# Adafruit_Metro_ESP32-S3.net
KiCad netlist of a schematic drawn in EAGLE
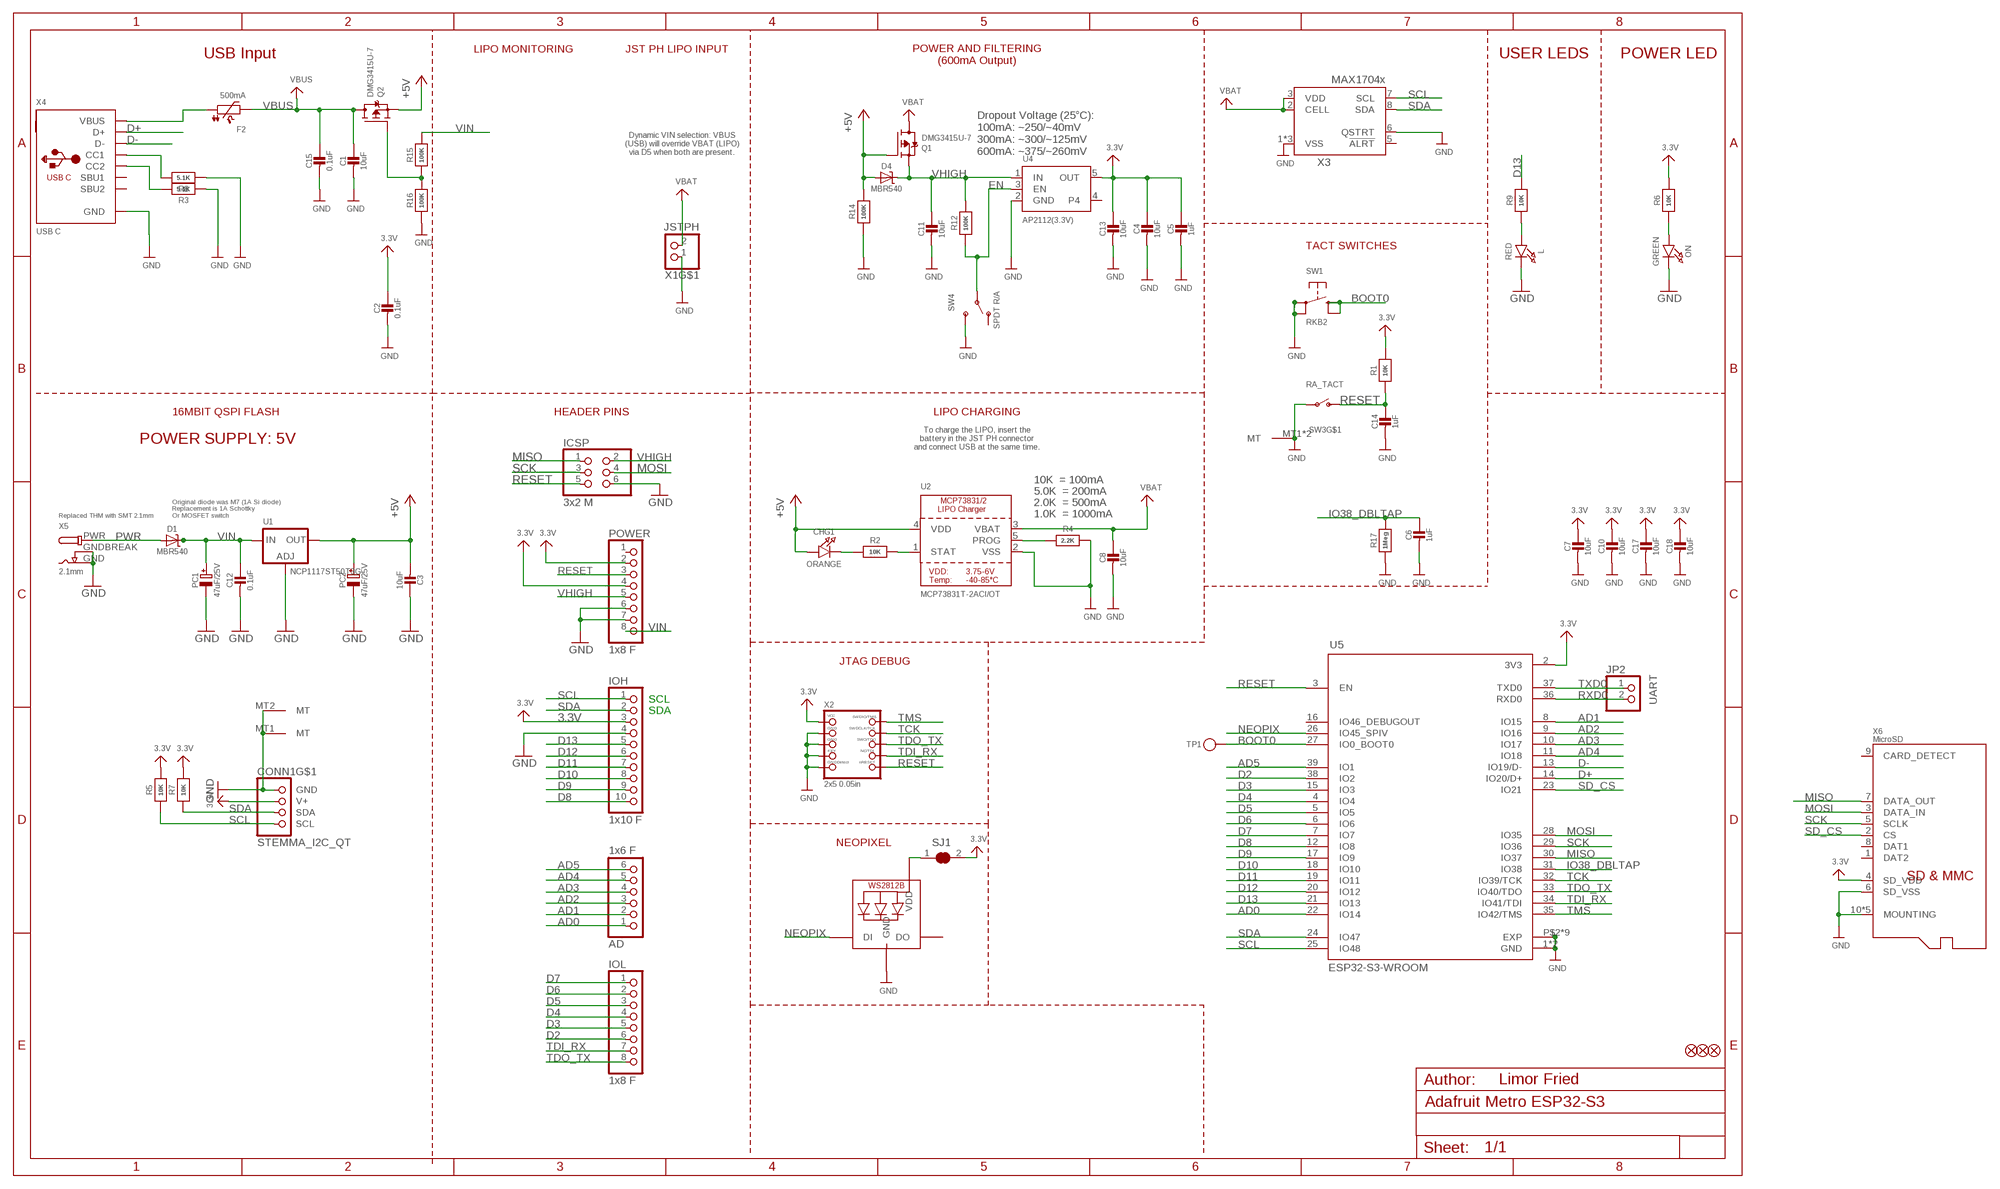
[diagram p0: schematic, sheet 1]

(export (version "E")
  (design (tool "Eeschema 10.0.6"))
  (components
    (comp (ref "AD")
      (value "1x6 F")
      (footprint "eagle-import:1X06_OVALWAVE")
      (libsource (lib "eagle-import") (part "HEADER-1X6OVALWAVE"))
    )
    (comp (ref "C1")
      (value "10uF")
      (footprint "eagle-import:0805-NO")
      (libsource (lib "eagle-import") (part "CAP_CERAMIC0805-NOOUTLINE"))
    )
    (comp (ref "C2")
      (value "0.1uF")
      (footprint "eagle-import:0603-NO")
      (libsource (lib "eagle-import") (part "CAP_CERAMIC0603_NO"))
    )
    (comp (ref "C3")
      (value "10uF")
      (footprint "eagle-import:0805-NO")
      (libsource (lib "eagle-import") (part "CAP_CERAMIC0805-NOOUTLINE"))
    )
    (comp (ref "C4")
      (value "10uF")
      (footprint "eagle-import:0805-NO")
      (libsource (lib "eagle-import") (part "CAP_CERAMIC0805-NOOUTLINE"))
    )
    (comp (ref "C5")
      (value "1uF")
      (footprint "eagle-import:0603-NO")
      (libsource (lib "eagle-import") (part "CAP_CERAMIC0603_NO"))
    )
    (comp (ref "C6")
      (value "1uF")
      (footprint "eagle-import:0603-NO")
      (libsource (lib "eagle-import") (part "CAP_CERAMIC0603_NO"))
    )
    (comp (ref "C7")
      (value "10uF")
      (footprint "eagle-import:0805-NO")
      (libsource (lib "eagle-import") (part "CAP_CERAMIC0805-NOOUTLINE"))
    )
    (comp (ref "C8")
      (value "10uF")
      (footprint "eagle-import:0805-NO")
      (libsource (lib "eagle-import") (part "CAP_CERAMIC0805-NOOUTLINE"))
    )
    (comp (ref "C10")
      (value "10uF")
      (footprint "eagle-import:0805-NO")
      (libsource (lib "eagle-import") (part "CAP_CERAMIC0805-NOOUTLINE"))
    )
    (comp (ref "C11")
      (value "10uF")
      (footprint "eagle-import:0805-NO")
      (libsource (lib "eagle-import") (part "CAP_CERAMIC0805-NOOUTLINE"))
    )
    (comp (ref "C12")
      (value "0.1uF")
      (footprint "eagle-import:0603-NO")
      (libsource (lib "eagle-import") (part "CAP_CERAMIC0603_NO"))
    )
    (comp (ref "C13")
      (value "10uF")
      (footprint "eagle-import:0805-NO")
      (libsource (lib "eagle-import") (part "CAP_CERAMIC0805-NOOUTLINE"))
    )
    (comp (ref "C14")
      (value "1uF")
      (footprint "eagle-import:0603-NO")
      (libsource (lib "eagle-import") (part "CAP_CERAMIC0603_NO"))
    )
    (comp (ref "C15")
      (value "0.1uF")
      (footprint "eagle-import:0603-NO")
      (libsource (lib "eagle-import") (part "CAP_CERAMIC0603_NO"))
    )
    (comp (ref "C17")
      (value "10uF")
      (footprint "eagle-import:0805-NO")
      (libsource (lib "eagle-import") (part "CAP_CERAMIC0805-NOOUTLINE"))
    )
    (comp (ref "C18")
      (value "10uF")
      (footprint "eagle-import:0805-NO")
      (libsource (lib "eagle-import") (part "CAP_CERAMIC0805-NOOUTLINE"))
    )
    (comp (ref "CHG1")
      (value "ORANGE")
      (footprint "eagle-import:CHIPLED_0603_NOOUTLINE")
      (libsource (lib "eagle-import") (part "LED0603_NOOUTLINE"))
    )
    (comp (ref "CONN1")
      (value "STEMMA_I2C_QT")
      (footprint "eagle-import:JST_SH4")
      (libsource (lib "eagle-import") (part "STEMMA_I2C_QT"))
    )
    (comp (ref "D1")
      (value "MBR540")
      (footprint "eagle-import:SOD-123")
      (libsource (lib "eagle-import") (part "DIODE-SCHOTTKYSOD-123"))
    )
    (comp (ref "D4")
      (value "MBR540")
      (footprint "eagle-import:SOD-123")
      (libsource (lib "eagle-import") (part "DIODE-SCHOTTKYSOD-123"))
    )
    (comp (ref "F2")
      (value "500mA")
      (footprint "eagle-import:0805-NO")
      (libsource (lib "eagle-import") (part "PTC_0805"))
    )
    (comp (ref "FD1")
      (value "FIDUCIAL_1MM")
      (footprint "eagle-import:FIDUCIAL_1MM")
      (libsource (lib "eagle-import") (part "FIDUCIAL_1MM"))
    )
    (comp (ref "FD2")
      (value "FIDUCIAL_1MM")
      (footprint "eagle-import:FIDUCIAL_1MM")
      (libsource (lib "eagle-import") (part "FIDUCIAL_1MM"))
    )
    (comp (ref "FD3")
      (value "FIDUCIAL_1MM")
      (footprint "eagle-import:FIDUCIAL_1MM")
      (libsource (lib "eagle-import") (part "FIDUCIAL_1MM"))
    )
    (comp (ref "ICSP")
      (value "3x2 M")
      (footprint "eagle-import:2X03_ROUND_70MIL")
      (libsource (lib "eagle-import") (part "HEADER-2X3"))
    )
    (comp (ref "IOH")
      (value "1x10 F")
      (footprint "eagle-import:1X10_OVALWAVE")
      (libsource (lib "eagle-import") (part "HEADER-1X10OVALWAVE"))
    )
    (comp (ref "IOL")
      (value "1x8 F")
      (footprint "eagle-import:1X08_OVALWAVE")
      (libsource (lib "eagle-import") (part "HEADER-1X8OVALWAVE"))
    )
    (comp (ref "JP2")
      (value "UART")
      (footprint "eagle-import:1X02_ROUND")
      (libsource (lib "eagle-import") (part "HEADER-1X2ROUND"))
    )
    (comp (ref "L")
      (value "RED")
      (footprint "eagle-import:CHIPLED_0603_NOOUTLINE")
      (libsource (lib "eagle-import") (part "LED0603_NOOUTLINE"))
    )
    (comp (ref "LED1")
      (value "WS2812B_3535FULL")
      (footprint "eagle-import:LED3535_FULLPADS")
      (libsource (lib "eagle-import") (part "WS2812B_3535FULL"))
    )
    (comp (ref "ON")
      (value "GREEN")
      (footprint "eagle-import:CHIPLED_0603_NOOUTLINE")
      (libsource (lib "eagle-import") (part "LED0603_NOOUTLINE"))
    )
    (comp (ref "PC1")
      (value "47uF/25V")
      (footprint "eagle-import:PANASONIC_D")
      (libsource (lib "eagle-import") (part "CAP_ELECTROLYTICPANASONIC_D"))
    )
    (comp (ref "PC2")
      (value "47uF/25V")
      (footprint "eagle-import:PANASONIC_D")
      (libsource (lib "eagle-import") (part "CAP_ELECTROLYTICPANASONIC_D"))
    )
    (comp (ref "POWER")
      (value "1x8 F")
      (footprint "eagle-import:1X08_OVALWAVE")
      (libsource (lib "eagle-import") (part "HEADER-1X8OVALWAVE"))
    )
    (comp (ref "Q1")
      (value "DMG3415U-7")
      (footprint "eagle-import:SOT23-R")
      (libsource (lib "eagle-import") (part "MOSFET-P"))
    )
    (comp (ref "Q2")
      (value "DMG3415U-7")
      (footprint "eagle-import:SOT23-R")
      (libsource (lib "eagle-import") (part "MOSFET-P"))
    )
    (comp (ref "R1")
      (value "10K")
      (footprint "eagle-import:0603-NO")
      (libsource (lib "eagle-import") (part "RESISTOR_0603_NOOUT"))
    )
    (comp (ref "R2")
      (value "10K")
      (footprint "eagle-import:0603-NO")
      (libsource (lib "eagle-import") (part "RESISTOR_0603_NOOUT"))
    )
    (comp (ref "R3")
      (value "5.1K")
      (footprint "eagle-import:0603-NO")
      (libsource (lib "eagle-import") (part "RESISTOR_0603_NOOUT"))
    )
    (comp (ref "R4")
      (value "2.2K")
      (footprint "eagle-import:0603-NO")
      (libsource (lib "eagle-import") (part "RESISTOR_0603_NOOUT"))
    )
    (comp (ref "R5")
      (value "10K")
      (footprint "eagle-import:0603-NO")
      (libsource (lib "eagle-import") (part "RESISTOR_0603_NOOUT"))
    )
    (comp (ref "R6")
      (value "10K")
      (footprint "eagle-import:0603-NO")
      (libsource (lib "eagle-import") (part "RESISTOR_0603_NOOUT"))
    )
    (comp (ref "R7")
      (value "10K")
      (footprint "eagle-import:0603-NO")
      (libsource (lib "eagle-import") (part "RESISTOR_0603_NOOUT"))
    )
    (comp (ref "R8")
      (value "5.1K")
      (footprint "eagle-import:0603-NO")
      (libsource (lib "eagle-import") (part "RESISTOR_0603_NOOUT"))
    )
    (comp (ref "R9")
      (value "10K")
      (footprint "eagle-import:0603-NO")
      (libsource (lib "eagle-import") (part "RESISTOR_0603_NOOUT"))
    )
    (comp (ref "R12")
      (value "100K")
      (footprint "eagle-import:0603-NO")
      (libsource (lib "eagle-import") (part "RESISTOR_0603_NOOUT"))
    )
    (comp (ref "R14")
      (value "100K")
      (footprint "eagle-import:0603-NO")
      (libsource (lib "eagle-import") (part "RESISTOR_0603_NOOUT"))
    )
    (comp (ref "R15")
      (value "100K")
      (footprint "eagle-import:0603-NO")
      (libsource (lib "eagle-import") (part "RESISTOR_0603_NOOUT"))
    )
    (comp (ref "R16")
      (value "100K")
      (footprint "eagle-import:0603-NO")
      (libsource (lib "eagle-import") (part "RESISTOR_0603_NOOUT"))
    )
    (comp (ref "R17")
      (value "1Meg")
      (footprint "eagle-import:0603-NO")
      (libsource (lib "eagle-import") (part "RESISTOR_0603_NOOUT"))
    )
    (comp (ref "SJ1")
      (value "SOLDERJUMPER_CLOSED")
      (footprint "eagle-import:SOLDERJUMPER_CLOSEDWIRE")
      (libsource (lib "eagle-import") (part "SOLDERJUMPER_CLOSED"))
    )
    (comp (ref "SW1")
      (value "RKB2")
      (footprint "eagle-import:BTN_RKB2_4.6X2.8")
      (libsource (lib "eagle-import") (part "SWITCH_TACT_SMT_RKB2"))
    )
    (comp (ref "SW3")
      (value "RA_TACT")
      (footprint "eagle-import:SPST_TACTILE_RA")
      (libsource (lib "eagle-import") (part "SWITCH_SPST_MNT_TACT_RA"))
    )
    (comp (ref "SW4")
      (value "SPDT R/A")
      (footprint "eagle-import:SPDT_SMT_SSSS811101")
      (libsource (lib "eagle-import") (part "SWITCH_SPDT"))
    )
    (comp (ref "TP1")
      (value "TESTPOINTROUND1.5MMNO")
      (footprint "eagle-import:TESTPOINT_ROUND_1.5MM_NO")
      (libsource (lib "eagle-import") (part "TESTPOINTROUND1.5MMNO"))
    )
    (comp (ref "U1")
      (value "NCP1117ST50T3G")
      (footprint "eagle-import:SOT223-R")
      (libsource (lib "eagle-import") (part "LM1117SOT223-REFLOW"))
    )
    (comp (ref "U2")
      (value "MCP73831T-2ACI/OT")
      (footprint "eagle-import:SOT23-5")
      (libsource (lib "eagle-import") (part "MCP73831/2"))
    )
    (comp (ref "U4")
      (value "AP2112(3.3V)")
      (footprint "eagle-import:SOT23-5")
      (fields (field (name "JLC_ROTATION") "0"))
      (libsource (lib "eagle-import") (part "VREG_SOT23-5"))
    )
    (comp (ref "U5")
      (value "ESP32-S3-WROOM")
      (footprint "eagle-import:S3-WROOM32")
      (libsource (lib "eagle-import") (part "ESP32-S3-WROOM"))
    )
    (comp (ref "X1")
      (value "JSTPH")
      (footprint "eagle-import:JSTPH2_BATT")
      (libsource (lib "eagle-import") (part "CON_JST_PH_2PIN_MT_BATT"))
    )
    (comp (ref "X2")
      (value "2x5 0.05in")
      (footprint "eagle-import:2X05_1.27MM_BOX_POSTS")
      (libsource (lib "eagle-import") (part "JTAG-CORTEXBOXPOSTS"))
    )
    (comp (ref "X3")
      (value "MAX17048/T")
      (footprint "eagle-import:TDFN8_2X2MM")
      (libsource (lib "eagle-import") (part "MAX17048/T"))
    )
    (comp (ref "X4")
      (value "USB C")
      (footprint "eagle-import:USB_C_CUSB31-CFM2AX-01-X")
      (libsource (lib "eagle-import") (part "USB_C"))
    )
    (comp (ref "X5")
      (value "2.1mm")
      (footprint "eagle-import:DCJACK_2MM_PTH")
      (libsource (lib "eagle-import") (part "DCBARRELPTH"))
    )
    (comp (ref "X6")
      (value "MicroSD")
      (footprint "eagle-import:MOLEX_104031-0811")
      (libsource (lib "eagle-import") (part "MICROSD104031-0811"))
    )
  )
  (nets
    (net (code "1") (name "+5V") (class "Default")
      (node (ref "C3") (pin "2") (pinfunction "2_2") (pintype "passive"))
      (node (ref "CHG1") (pin "A") (pinfunction "A_A") (pintype "passive"))
      (node (ref "D4") (pin "A") (pinfunction "A_A") (pintype "passive"))
      (node (ref "PC2") (pin "+") (pinfunction "+_+") (pintype "passive"))
      (node (ref "Q1") (pin "1") (pinfunction "G_1") (pintype "passive"))
      (node (ref "Q2") (pin "2") (pinfunction "S_2") (pintype "passive"))
      (node (ref "R14") (pin "2") (pinfunction "2_2") (pintype "passive"))
      (node (ref "U1") (pin "2") (pinfunction "OUT_2") (pintype "passive"))
      (node (ref "U1") (pin "4") (pinfunction "OUT_4") (pintype "passive"))
      (node (ref "U2") (pin "4") (pinfunction "VDD_4") (pintype "power_in"))
    )
    (net (code "2") (name "/AD0") (class "Default")
      (node (ref "AD") (pin "1") (pinfunction "1_1") (pintype "passive"))
      (node (ref "U5") (pin "22") (pinfunction "IO14_22") (pintype "bidirectional"))
    )
    (net (code "3") (name "/AD1") (class "Default")
      (node (ref "AD") (pin "2") (pinfunction "2_2") (pintype "passive"))
      (node (ref "U5") (pin "8") (pinfunction "IO15_8") (pintype "bidirectional"))
    )
    (net (code "4") (name "/AD2") (class "Default")
      (node (ref "AD") (pin "3") (pinfunction "3_3") (pintype "passive"))
      (node (ref "U5") (pin "9") (pinfunction "IO16_9") (pintype "bidirectional"))
    )
    (net (code "5") (name "/AD3") (class "Default")
      (node (ref "AD") (pin "4") (pinfunction "4_4") (pintype "passive"))
      (node (ref "U5") (pin "10") (pinfunction "IO17_10") (pintype "bidirectional"))
    )
    (net (code "6") (name "/AD4") (class "Default")
      (node (ref "AD") (pin "5") (pinfunction "5_5") (pintype "passive"))
      (node (ref "U5") (pin "11") (pinfunction "IO18_11") (pintype "bidirectional"))
    )
    (net (code "7") (name "/AD5") (class "Default")
      (node (ref "AD") (pin "6") (pinfunction "6_6") (pintype "passive"))
      (node (ref "U5") (pin "39") (pinfunction "IO1_39") (pintype "bidirectional"))
    )
    (net (code "8") (name "/BOOT0") (class "Default")
      (node (ref "SW1") (pin "B") (pinfunction "S_B") (pintype "passive"))
      (node (ref "SW1") (pin "B'") (pinfunction "S1_B'") (pintype "passive"))
      (node (ref "TP1") (pin "P$1") (pinfunction "P$1_P$1") (pintype "bidirectional"))
      (node (ref "U5") (pin "27") (pinfunction "IO0_BOOT0_27") (pintype "bidirectional"))
    )
    (net (code "9") (name "/D+") (class "Default")
      (node (ref "U5") (pin "14") (pinfunction "IO20/D+_14") (pintype "bidirectional"))
      (node (ref "X4") (pin "A6") (pinfunction "D+_A6") (pintype "bidirectional"))
      (node (ref "X4") (pin "B6") (pinfunction "D+_B6") (pintype "bidirectional"))
    )
    (net (code "10") (name "/D-") (class "Default")
      (node (ref "U5") (pin "13") (pinfunction "IO19/D-_13") (pintype "bidirectional"))
      (node (ref "X4") (pin "A7") (pinfunction "D-_A7") (pintype "bidirectional"))
      (node (ref "X4") (pin "B7") (pinfunction "D-_B7") (pintype "bidirectional"))
    )
    (net (code "11") (name "/D2") (class "Default")
      (node (ref "IOL") (pin "6") (pinfunction "6_6") (pintype "passive"))
      (node (ref "U5") (pin "38") (pinfunction "IO2_38") (pintype "bidirectional"))
    )
    (net (code "12") (name "/D3") (class "Default")
      (node (ref "IOL") (pin "5") (pinfunction "5_5") (pintype "passive"))
      (node (ref "U5") (pin "15") (pinfunction "IO3_15") (pintype "bidirectional"))
    )
    (net (code "13") (name "/D4") (class "Default")
      (node (ref "IOL") (pin "4") (pinfunction "4_4") (pintype "passive"))
      (node (ref "U5") (pin "4") (pinfunction "IO4_4") (pintype "bidirectional"))
    )
    (net (code "14") (name "/D5") (class "Default")
      (node (ref "IOL") (pin "3") (pinfunction "3_3") (pintype "passive"))
      (node (ref "U5") (pin "5") (pinfunction "IO5_5") (pintype "bidirectional"))
    )
    (net (code "15") (name "/D6") (class "Default")
      (node (ref "IOL") (pin "2") (pinfunction "2_2") (pintype "passive"))
      (node (ref "U5") (pin "6") (pinfunction "IO6_6") (pintype "bidirectional"))
    )
    (net (code "16") (name "/D7") (class "Default")
      (node (ref "IOL") (pin "1") (pinfunction "1_1") (pintype "passive"))
      (node (ref "U5") (pin "7") (pinfunction "IO7_7") (pintype "bidirectional"))
    )
    (net (code "17") (name "/D8") (class "Default")
      (node (ref "IOH") (pin "10") (pinfunction "10_10") (pintype "passive"))
      (node (ref "U5") (pin "12") (pinfunction "IO8_12") (pintype "bidirectional"))
    )
    (net (code "18") (name "/D9") (class "Default")
      (node (ref "IOH") (pin "9") (pinfunction "9_9") (pintype "passive"))
      (node (ref "U5") (pin "17") (pinfunction "IO9_17") (pintype "bidirectional"))
    )
    (net (code "19") (name "/D10") (class "Default")
      (node (ref "IOH") (pin "8") (pinfunction "8_8") (pintype "passive"))
      (node (ref "U5") (pin "18") (pinfunction "IO10_18") (pintype "bidirectional"))
    )
    (net (code "20") (name "/D11") (class "Default")
      (node (ref "IOH") (pin "7") (pinfunction "7_7") (pintype "passive"))
      (node (ref "U5") (pin "19") (pinfunction "IO11_19") (pintype "bidirectional"))
    )
    (net (code "21") (name "/D12") (class "Default")
      (node (ref "IOH") (pin "6") (pinfunction "6_6") (pintype "passive"))
      (node (ref "U5") (pin "20") (pinfunction "IO12_20") (pintype "bidirectional"))
    )
    (net (code "22") (name "/D13") (class "Default")
      (node (ref "IOH") (pin "5") (pinfunction "5_5") (pintype "passive"))
      (node (ref "R9") (pin "2") (pinfunction "2_2") (pintype "passive"))
      (node (ref "U5") (pin "21") (pinfunction "IO13_21") (pintype "bidirectional"))
    )
    (net (code "23") (name "/EN") (class "Default")
      (node (ref "R12") (pin "1") (pinfunction "1_1") (pintype "passive"))
      (node (ref "SW4") (pin "B") (pinfunction "P_B") (pintype "passive"))
      (node (ref "U4") (pin "3") (pinfunction "EN_3") (pintype "input"))
    )
    (net (code "24") (name "/IO38_DBLTAP") (class "Default")
      (node (ref "C6") (pin "1") (pinfunction "1_1") (pintype "passive"))
      (node (ref "R17") (pin "2") (pinfunction "2_2") (pintype "passive"))
      (node (ref "U5") (pin "31") (pinfunction "IO38_31") (pintype "bidirectional"))
    )
    (net (code "25") (name "/MISO") (class "Default")
      (node (ref "ICSP") (pin "1") (pinfunction "1_1") (pintype "passive"))
      (node (ref "U5") (pin "30") (pinfunction "IO37_30") (pintype "bidirectional"))
      (node (ref "X6") (pin "7") (pinfunction "DATA_OUT_7") (pintype "output"))
    )
    (net (code "26") (name "/MOSI") (class "Default")
      (node (ref "ICSP") (pin "4") (pinfunction "4_4") (pintype "passive"))
      (node (ref "U5") (pin "28") (pinfunction "IO35_28") (pintype "input"))
      (node (ref "X6") (pin "3") (pinfunction "DATA_IN_3") (pintype "input"))
    )
    (net (code "27") (name "/NEOPIX") (class "Default")
      (node (ref "LED1") (pin "1") (pinfunction "DI_1") (pintype "input"))
      (node (ref "U5") (pin "26") (pinfunction "IO45_SPIV_26") (pintype "bidirectional"))
    )
    (net (code "28") (name "/PWR") (class "Default")
      (node (ref "D1") (pin "A") (pinfunction "A_A") (pintype "passive"))
      (node (ref "X5") (pin "PWR") (pinfunction "PWR_PWR") (pintype "power_in"))
    )
    (net (code "29") (name "/RESET") (class "Default")
      (node (ref "C14") (pin "1") (pinfunction "1_1") (pintype "passive"))
      (node (ref "ICSP") (pin "5") (pinfunction "5_5") (pintype "passive"))
      (node (ref "POWER") (pin "3") (pinfunction "3_3") (pintype "passive"))
      (node (ref "R1") (pin "1") (pinfunction "1_1") (pintype "passive"))
      (node (ref "SW3") (pin "2") (pinfunction "S_2") (pintype "passive"))
      (node (ref "U5") (pin "3") (pinfunction "EN_3") (pintype "input"))
      (node (ref "X2") (pin "10") (pinfunction "NRESET_10") (pintype "bidirectional"))
    )
    (net (code "30") (name "/RXD0") (class "Default")
      (node (ref "JP2") (pin "2") (pinfunction "2_2") (pintype "passive"))
      (node (ref "U5") (pin "36") (pinfunction "RXD0_36") (pintype "bidirectional"))
    )
    (net (code "31") (name "/SCK") (class "Default")
      (node (ref "ICSP") (pin "3") (pinfunction "3_3") (pintype "passive"))
      (node (ref "U5") (pin "29") (pinfunction "IO36_29") (pintype "bidirectional"))
      (node (ref "X6") (pin "5") (pinfunction "SCLK_5") (pintype "input"))
    )
    (net (code "32") (name "/SCL") (class "Default")
      (node (ref "CONN1") (pin "4") (pinfunction "SCL_4") (pintype "passive"))
      (node (ref "IOH") (pin "1") (pinfunction "1_1") (pintype "passive"))
      (node (ref "R5") (pin "1") (pinfunction "1_1") (pintype "passive"))
      (node (ref "U5") (pin "25") (pinfunction "IO48_25") (pintype "input"))
      (node (ref "X3") (pin "7") (pinfunction "SCL_7") (pintype "bidirectional"))
    )
    (net (code "33") (name "/SDA") (class "Default")
      (node (ref "CONN1") (pin "3") (pinfunction "SDA_3") (pintype "passive"))
      (node (ref "IOH") (pin "2") (pinfunction "2_2") (pintype "passive"))
      (node (ref "R7") (pin "1") (pinfunction "1_1") (pintype "passive"))
      (node (ref "U5") (pin "24") (pinfunction "IO47_24") (pintype "bidirectional"))
      (node (ref "X3") (pin "8") (pinfunction "SDA_8") (pintype "bidirectional"))
    )
    (net (code "34") (name "/SD_CS") (class "Default")
      (node (ref "U5") (pin "23") (pinfunction "IO21_23") (pintype "bidirectional"))
      (node (ref "X6") (pin "2") (pinfunction "CS_2") (pintype "input"))
    )
    (net (code "35") (name "/TCK") (class "Default")
      (node (ref "U5") (pin "32") (pinfunction "IO39/TCK_32") (pintype "bidirectional"))
      (node (ref "X2") (pin "4") (pinfunction "SWDCLK_4") (pintype "bidirectional"))
    )
    (net (code "36") (name "/TDI_RX") (class "Default")
      (node (ref "IOL") (pin "7") (pinfunction "7_7") (pintype "passive"))
      (node (ref "U5") (pin "34") (pinfunction "IO41/TDI_34") (pintype "bidirectional"))
      (node (ref "X2") (pin "8") (pinfunction "TDI_8") (pintype "bidirectional"))
    )
    (net (code "37") (name "/TDO_TX") (class "Default")
      (node (ref "IOL") (pin "8") (pinfunction "8_8") (pintype "passive"))
      (node (ref "U5") (pin "33") (pinfunction "IO40/TDO_33") (pintype "bidirectional"))
      (node (ref "X2") (pin "6") (pinfunction "SWO_6") (pintype "bidirectional"))
    )
    (net (code "38") (name "/TMS") (class "Default")
      (node (ref "U5") (pin "35") (pinfunction "IO42/TMS_35") (pintype "bidirectional"))
      (node (ref "X2") (pin "2") (pinfunction "SWDIO_2") (pintype "bidirectional"))
    )
    (net (code "39") (name "/TXD0") (class "Default")
      (node (ref "JP2") (pin "1") (pinfunction "1_1") (pintype "passive"))
      (node (ref "U5") (pin "37") (pinfunction "TXD0_37") (pintype "bidirectional"))
    )
    (net (code "40") (name "/VHIGH") (class "Default")
      (node (ref "C11") (pin "1") (pinfunction "1_1") (pintype "passive"))
      (node (ref "D4") (pin "C") (pinfunction "C_C") (pintype "passive"))
      (node (ref "ICSP") (pin "2") (pinfunction "2_2") (pintype "passive"))
      (node (ref "POWER") (pin "5") (pinfunction "5_5") (pintype "passive"))
      (node (ref "Q1") (pin "2") (pinfunction "S_2") (pintype "passive"))
      (node (ref "R12") (pin "2") (pinfunction "2_2") (pintype "passive"))
      (node (ref "U4") (pin "1") (pinfunction "IN_1") (pintype "power_in"))
    )
    (net (code "41") (name "/VIN") (class "Default")
      (node (ref "C12") (pin "1") (pinfunction "1_1") (pintype "passive"))
      (node (ref "D1") (pin "C") (pinfunction "C_C") (pintype "passive"))
      (node (ref "PC1") (pin "+") (pinfunction "+_+") (pintype "passive"))
      (node (ref "POWER") (pin "8") (pinfunction "8_8") (pintype "passive"))
      (node (ref "R15") (pin "2") (pinfunction "2_2") (pintype "passive"))
      (node (ref "U1") (pin "3") (pinfunction "IN_3") (pintype "input"))
    )
    (net (code "42") (name "3.3V") (class "Default")
      (node (ref "C10") (pin "1") (pinfunction "1_1") (pintype "passive"))
      (node (ref "C13") (pin "1") (pinfunction "1_1") (pintype "passive"))
      (node (ref "C17") (pin "1") (pinfunction "1_1") (pintype "passive"))
      (node (ref "C18") (pin "1") (pinfunction "1_1") (pintype "passive"))
      (node (ref "C2") (pin "1") (pinfunction "1_1") (pintype "passive"))
      (node (ref "C4") (pin "1") (pinfunction "1_1") (pintype "passive"))
      (node (ref "C5") (pin "1") (pinfunction "1_1") (pintype "passive"))
      (node (ref "C7") (pin "1") (pinfunction "1_1") (pintype "passive"))
      (node (ref "CONN1") (pin "2") (pinfunction "V+_2") (pintype "passive"))
      (node (ref "IOH") (pin "3") (pinfunction "3_3") (pintype "passive"))
      (node (ref "POWER") (pin "2") (pinfunction "2_2") (pintype "passive"))
      (node (ref "POWER") (pin "4") (pinfunction "4_4") (pintype "passive"))
      (node (ref "R1") (pin "2") (pinfunction "2_2") (pintype "passive"))
      (node (ref "R5") (pin "2") (pinfunction "2_2") (pintype "passive"))
      (node (ref "R6") (pin "2") (pinfunction "2_2") (pintype "passive"))
      (node (ref "R7") (pin "2") (pinfunction "2_2") (pintype "passive"))
      (node (ref "SJ1") (pin "2") (pinfunction "2_2") (pintype "passive"))
      (node (ref "U4") (pin "5") (pinfunction "OUT_5") (pintype "power_in"))
      (node (ref "U5") (pin "2") (pinfunction "3V3_2") (pintype "power_in"))
      (node (ref "X2") (pin "1") (pinfunction "VCC_1") (pintype "power_in"))
      (node (ref "X6") (pin "4") (pinfunction "SD_VDD_4") (pintype "power_in"))
    )
    (net (code "43") (name "GND") (class "Default")
      (node (ref "C1") (pin "2") (pinfunction "2_2") (pintype "passive"))
      (node (ref "C10") (pin "2") (pinfunction "2_2") (pintype "passive"))
      (node (ref "C11") (pin "2") (pinfunction "2_2") (pintype "passive"))
      (node (ref "C12") (pin "2") (pinfunction "2_2") (pintype "passive"))
      (node (ref "C13") (pin "2") (pinfunction "2_2") (pintype "passive"))
      (node (ref "C14") (pin "2") (pinfunction "2_2") (pintype "passive"))
      (node (ref "C15") (pin "2") (pinfunction "2_2") (pintype "passive"))
      (node (ref "C17") (pin "2") (pinfunction "2_2") (pintype "passive"))
      (node (ref "C18") (pin "2") (pinfunction "2_2") (pintype "passive"))
      (node (ref "C2") (pin "2") (pinfunction "2_2") (pintype "passive"))
      (node (ref "C3") (pin "1") (pinfunction "1_1") (pintype "passive"))
      (node (ref "C4") (pin "2") (pinfunction "2_2") (pintype "passive"))
      (node (ref "C5") (pin "2") (pinfunction "2_2") (pintype "passive"))
      (node (ref "C6") (pin "2") (pinfunction "2_2") (pintype "passive"))
      (node (ref "C7") (pin "2") (pinfunction "2_2") (pintype "passive"))
      (node (ref "C8") (pin "2") (pinfunction "2_2") (pintype "passive"))
      (node (ref "CONN1") (pin "1") (pinfunction "GND_1") (pintype "passive"))
      (node (ref "CONN1") (pin "MT1") (pinfunction "MT_MT1") (pintype "bidirectional"))
      (node (ref "CONN1") (pin "MT2") (pinfunction "MT_MT2") (pintype "bidirectional"))
      (node (ref "ICSP") (pin "6") (pinfunction "6_6") (pintype "passive"))
      (node (ref "IOH") (pin "4") (pinfunction "4_4") (pintype "passive"))
      (node (ref "L") (pin "C") (pinfunction "C_C") (pintype "passive"))
      (node (ref "LED1") (pin "4") (pinfunction "GND_4") (pintype "power_in"))
      (node (ref "ON") (pin "C") (pinfunction "C_C") (pintype "passive"))
      (node (ref "PC1") (pin "-") (pinfunction "-_-") (pintype "passive"))
      (node (ref "PC2") (pin "-") (pinfunction "-_-") (pintype "passive"))
      (node (ref "POWER") (pin "6") (pinfunction "6_6") (pintype "passive"))
      (node (ref "POWER") (pin "7") (pinfunction "7_7") (pintype "passive"))
      (node (ref "R14") (pin "1") (pinfunction "1_1") (pintype "passive"))
      (node (ref "R16") (pin "1") (pinfunction "1_1") (pintype "passive"))
      (node (ref "R17") (pin "1") (pinfunction "1_1") (pintype "passive"))
      (node (ref "R3") (pin "1") (pinfunction "1_1") (pintype "passive"))
      (node (ref "R4") (pin "2") (pinfunction "2_2") (pintype "passive"))
      (node (ref "R8") (pin "1") (pinfunction "1_1") (pintype "passive"))
      (node (ref "SW1") (pin "A") (pinfunction "P_A") (pintype "passive"))
      (node (ref "SW1") (pin "A'") (pinfunction "P1_A'") (pintype "passive"))
      (node (ref "SW3") (pin "1") (pinfunction "P_1") (pintype "passive"))
      (node (ref "SW3") (pin "MT1") (pinfunction "MT_MT1") (pintype "bidirectional"))
      (node (ref "SW3") (pin "MT2") (pinfunction "MT_MT2") (pintype "bidirectional"))
      (node (ref "SW4") (pin "C") (pinfunction "S_C") (pintype "passive"))
      (node (ref "U1") (pin "1") (pinfunction "ADJ_1") (pintype "input"))
      (node (ref "U2") (pin "2") (pinfunction "VSS_2") (pintype "power_in"))
      (node (ref "U4") (pin "2") (pinfunction "GND_2") (pintype "power_in"))
      (node (ref "U5") (pin "1") (pinfunction "GND_1") (pintype "power_in"))
      (node (ref "U5") (pin "40") (pinfunction "GND_40") (pintype "power_in"))
      (node (ref "U5") (pin "P$10") (pinfunction "EXP_P$10") (pintype "power_in"))
      (node (ref "U5") (pin "P$2") (pinfunction "EXP_P$2") (pintype "power_in"))
      (node (ref "U5") (pin "P$3") (pinfunction "EXP_P$3") (pintype "power_in"))
      (node (ref "U5") (pin "P$4") (pinfunction "EXP_P$4") (pintype "power_in"))
      (node (ref "U5") (pin "P$5") (pinfunction "EXP_P$5") (pintype "power_in"))
      (node (ref "U5") (pin "P$6") (pinfunction "EXP_P$6") (pintype "power_in"))
      (node (ref "U5") (pin "P$7") (pinfunction "EXP_P$7") (pintype "power_in"))
      (node (ref "U5") (pin "P$8") (pinfunction "EXP_P$8") (pintype "power_in"))
      (node (ref "U5") (pin "P$9") (pinfunction "EXP_P$9") (pintype "power_in"))
      (node (ref "X1") (pin "1") (pinfunction "1_1") (pintype "passive"))
      (node (ref "X2") (pin "3") (pinfunction "GND_3") (pintype "power_in"))
      (node (ref "X2") (pin "5") (pinfunction "GND_5") (pintype "power_in"))
      (node (ref "X2") (pin "7") (pinfunction "KEY_7") (pintype "bidirectional"))
      (node (ref "X2") (pin "9") (pinfunction "GNDDETECT_9") (pintype "bidirectional"))
      (node (ref "X3") (pin "1") (pinfunction "VSS_1") (pintype "power_in"))
      (node (ref "X3") (pin "4") (pinfunction "VSS_4") (pintype "power_in"))
      (node (ref "X3") (pin "6") (pinfunction "QSTRT_6") (pintype "input"))
      (node (ref "X3") (pin "THERMAL") (pinfunction "VSS_THERMAL") (pintype "power_in"))
      (node (ref "X4") (pin "A1B12") (pinfunction "GND_A1B12") (pintype "power_in"))
      (node (ref "X4") (pin "B1A12") (pinfunction "GND_B1A12") (pintype "power_in"))
      (node (ref "X5") (pin "GND") (pinfunction "GND_GND") (pintype "power_in"))
      (node (ref "X5") (pin "GNDBREAK") (pinfunction "GNDBREAK_GNDBREAK") (pintype "power_in"))
      (node (ref "X6") (pin "10") (pinfunction "MOUNTING_10") (pintype "passive"))
      (node (ref "X6") (pin "6") (pinfunction "SD_VSS_6") (pintype "power_in"))
      (node (ref "X6") (pin "G1") (pinfunction "MOUNTING_G1") (pintype "passive"))
      (node (ref "X6") (pin "G2") (pinfunction "MOUNTING_G2") (pintype "passive"))
      (node (ref "X6") (pin "G3") (pinfunction "MOUNTING_G3") (pintype "passive"))
      (node (ref "X6") (pin "G4") (pinfunction "MOUNTING_G4") (pintype "passive"))
    )
    (net (code "44") (name "Net-(CHG1-PadC)") (class "Default")
      (node (ref "CHG1") (pin "C") (pinfunction "C_C") (pintype "passive"))
      (node (ref "R2") (pin "1") (pinfunction "1_1") (pintype "passive"))
    )
    (net (code "45") (name "Net-(F2-Pad1)") (class "Default")
      (node (ref "F2") (pin "1") (pinfunction "1_1") (pintype "passive"))
      (node (ref "X4") (pin "A4B9") (pinfunction "VBUS_A4B9") (pintype "power_in"))
      (node (ref "X4") (pin "B4A9") (pinfunction "VBUS_B4A9") (pintype "power_in"))
    )
    (net (code "46") (name "Net-(L-PadA)") (class "Default")
      (node (ref "L") (pin "A") (pinfunction "A_A") (pintype "passive"))
      (node (ref "R9") (pin "1") (pinfunction "1_1") (pintype "passive"))
    )
    (net (code "47") (name "Net-(LED1-VDD)") (class "Default")
      (node (ref "LED1") (pin "2") (pinfunction "VDD_2") (pintype "power_in"))
      (node (ref "SJ1") (pin "1") (pinfunction "1_1") (pintype "passive"))
    )
    (net (code "48") (name "Net-(ON-PadA)") (class "Default")
      (node (ref "ON") (pin "A") (pinfunction "A_A") (pintype "passive"))
      (node (ref "R6") (pin "1") (pinfunction "1_1") (pintype "passive"))
    )
    (net (code "49") (name "Net-(Q2-G)") (class "Default")
      (node (ref "Q2") (pin "1") (pinfunction "G_1") (pintype "passive"))
      (node (ref "R15") (pin "1") (pinfunction "1_1") (pintype "passive"))
      (node (ref "R16") (pin "2") (pinfunction "2_2") (pintype "passive"))
    )
    (net (code "50") (name "Net-(U2-PROG)") (class "Default")
      (node (ref "R4") (pin "1") (pinfunction "1_1") (pintype "passive"))
      (node (ref "U2") (pin "5") (pinfunction "PROG_5") (pintype "input"))
    )
    (net (code "51") (name "Net-(U2-STAT)") (class "Default")
      (node (ref "R2") (pin "2") (pinfunction "2_2") (pintype "passive"))
      (node (ref "U2") (pin "1") (pinfunction "STAT_1") (pintype "output"))
    )
    (net (code "52") (name "Net-(X4-CC1)") (class "Default")
      (node (ref "R8") (pin "2") (pinfunction "2_2") (pintype "passive"))
      (node (ref "X4") (pin "A5") (pinfunction "CC1_A5") (pintype "bidirectional"))
    )
    (net (code "53") (name "Net-(X4-CC2)") (class "Default")
      (node (ref "R3") (pin "2") (pinfunction "2_2") (pintype "passive"))
      (node (ref "X4") (pin "B5") (pinfunction "CC2_B5") (pintype "bidirectional"))
    )
    (net (code "54") (name "VBAT") (class "Default")
      (node (ref "C8") (pin "1") (pinfunction "1_1") (pintype "passive"))
      (node (ref "Q1") (pin "3") (pinfunction "D_3") (pintype "passive"))
      (node (ref "U2") (pin "3") (pinfunction "VBAT_3") (pintype "power_in"))
      (node (ref "X1") (pin "2") (pinfunction "2_2") (pintype "passive"))
      (node (ref "X3") (pin "2") (pinfunction "CELL_2") (pintype "power_in"))
      (node (ref "X3") (pin "3") (pinfunction "VDD_3") (pintype "power_in"))
    )
    (net (code "55") (name "VBUS") (class "Default")
      (node (ref "C1") (pin "1") (pinfunction "1_1") (pintype "passive"))
      (node (ref "C15") (pin "1") (pinfunction "1_1") (pintype "passive"))
      (node (ref "F2") (pin "2") (pinfunction "2_2") (pintype "passive"))
      (node (ref "Q2") (pin "3") (pinfunction "D_3") (pintype "passive"))
    )
    (net (code "56") (name "unconnected-(LED1-DO-Pad3)") (class "Default")
      (node (ref "LED1") (pin "3") (pinfunction "DO_3") (pintype "output"))
    )
    (net (code "57") (name "unconnected-(POWER-Pad1)") (class "Default")
      (node (ref "POWER") (pin "1") (pinfunction "1_1") (pintype "passive"))
    )
    (net (code "58") (name "unconnected-(SW4-O-PadA)") (class "Default")
      (node (ref "SW4") (pin "A") (pinfunction "O_A") (pintype "passive"))
    )
    (net (code "59") (name "unconnected-(U4-P4-Pad4)") (class "Default")
      (node (ref "U4") (pin "4") (pinfunction "P4_4") (pintype "bidirectional"))
    )
    (net (code "60") (name "unconnected-(U5-IO46_DEBUGOUT-Pad16)") (class "Default")
      (node (ref "U5") (pin "16") (pinfunction "IO46_DEBUGOUT_16") (pintype "input"))
    )
    (net (code "61") (name "unconnected-(X3-~{ALRT}-Pad5)") (class "Default")
      (node (ref "X3") (pin "5") (pinfunction "~{ALRT}_5") (pintype "output"))
    )
    (net (code "62") (name "unconnected-(X4-SBU1-PadA8)") (class "Default")
      (node (ref "X4") (pin "A8") (pinfunction "SBU1_A8") (pintype "bidirectional"))
    )
    (net (code "63") (name "unconnected-(X4-SBU2-PadB8)") (class "Default")
      (node (ref "X4") (pin "B8") (pinfunction "SBU2_B8") (pintype "bidirectional"))
    )
    (net (code "64") (name "unconnected-(X6-CARD_DETECT-Pad9)") (class "Default")
      (node (ref "X6") (pin "9") (pinfunction "CARD_DETECT_9") (pintype "passive"))
    )
    (net (code "65") (name "unconnected-(X6-DAT1-Pad8)") (class "Default")
      (node (ref "X6") (pin "8") (pinfunction "DAT1_8") (pintype "bidirectional"))
    )
    (net (code "66") (name "unconnected-(X6-DAT2-Pad1)") (class "Default")
      (node (ref "X6") (pin "1") (pinfunction "DAT2_1") (pintype "bidirectional"))
    )
  )
)
